# Schematic_altium.net
KiCad netlist of a schematic drawn in Altium Designer
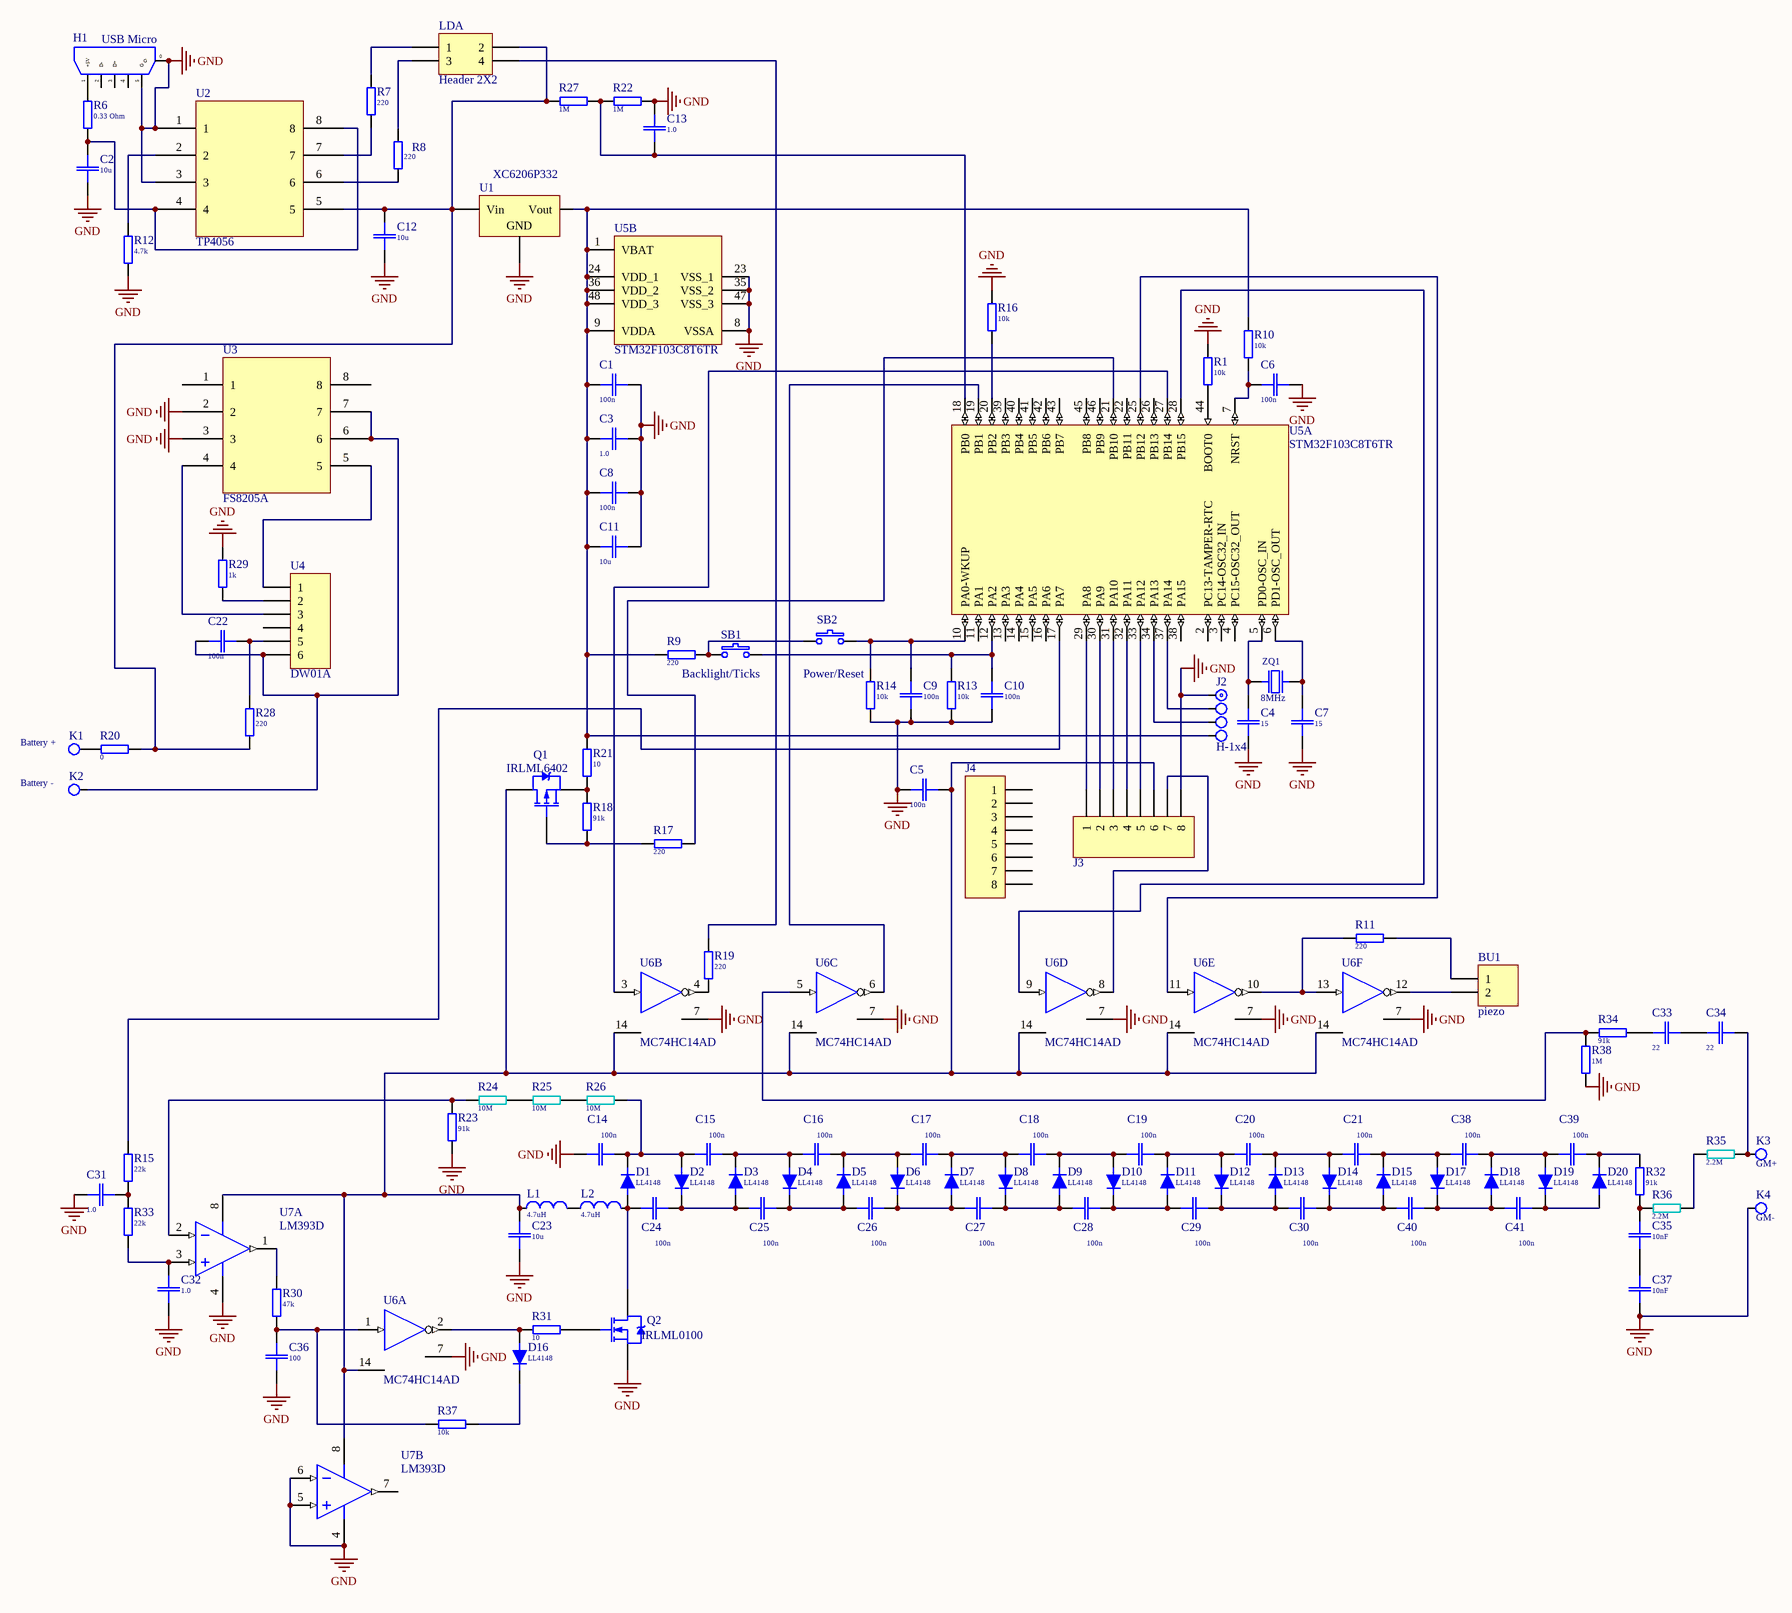
[diagram p0: Schematic_altium.SchDoc]

(export (version "E")
  (design (tool "Eeschema 10.0.6"))
  (components
    (comp (ref "BU1")
      (value "piezo")
      (footprint "HDR1X2")
      (description "Header, 2-Pin")
      (fields (field (name "PUBLISHER") "Altium Limited"))
      (libsource (lib "Miscellaneous Connectors") (part "Header 2"))
    )
    (comp (ref "C1")
      (value "100n")
      (footprint "C0805(2013)")
      (description "SMD-0805")
      (libsource (lib "SMD-RCL") (part "C-0805"))
    )
    (comp (ref "C2")
      (value "10u")
      (footprint "C1210(3225)")
      (description "SMD-1210 100V X7R 10%")
      (libsource (lib "SMD-RCL") (part "C-1210  100V 2.2u"))
    )
    (comp (ref "C3")
      (value "1.0")
      (footprint "C0805(2013)")
      (description "SMD-0805")
      (libsource (lib "SMD-RCL") (part "C-0805"))
    )
    (comp (ref "C4")
      (value "15")
      (footprint "C0805(2013)")
      (description "SMD-0805")
      (libsource (lib "SMD-RCL") (part "C-0805"))
    )
    (comp (ref "C5")
      (value "100n")
      (footprint "C0805(2013)")
      (description "SMD-0805")
      (libsource (lib "SMD-RCL") (part "C-0805"))
    )
    (comp (ref "C6")
      (value "100n")
      (footprint "C0805(2013)")
      (description "SMD-0805")
      (libsource (lib "SMD-RCL") (part "C-0805"))
    )
    (comp (ref "C7")
      (value "15")
      (footprint "C0805(2013)")
      (description "SMD-0805")
      (libsource (lib "SMD-RCL") (part "C-0805"))
    )
    (comp (ref "C8")
      (value "100n")
      (footprint "C0805(2013)")
      (description "SMD-0805")
      (libsource (lib "SMD-RCL") (part "C-0805"))
    )
    (comp (ref "C9")
      (value "100n")
      (footprint "C0805(2013)")
      (description "SMD-0805")
      (libsource (lib "SMD-RCL") (part "C-0805"))
    )
    (comp (ref "C10")
      (value "100n")
      (footprint "C0805(2013)")
      (description "SMD-0805")
      (libsource (lib "SMD-RCL") (part "C-0805"))
    )
    (comp (ref "C11")
      (value "10u")
      (footprint "C1210(3225)")
      (description "SMD-1210 100V X7R 10%")
      (libsource (lib "SMD-RCL") (part "C-1210  100V 2.2u"))
    )
    (comp (ref "C12")
      (value "10u")
      (footprint "C1210(3225)")
      (description "SMD-1210 100V X7R 10%")
      (libsource (lib "SMD-RCL") (part "C-1210  100V 2.2u"))
    )
    (comp (ref "C13")
      (value "1.0")
      (footprint "C0805(2013)")
      (description "SMD-0805")
      (libsource (lib "SMD-RCL") (part "C-0805"))
    )
    (comp (ref "C14")
      (value "100n")
      (footprint "C0805(2013)")
      (description "SMD-0805")
      (libsource (lib "SMD-RCL") (part "C-0805"))
    )
    (comp (ref "C15")
      (value "100n")
      (footprint "C0805(2013)")
      (description "SMD-0805")
      (libsource (lib "SMD-RCL") (part "C-0805"))
    )
    (comp (ref "C16")
      (value "100n")
      (footprint "C0805(2013)")
      (description "SMD-0805")
      (libsource (lib "SMD-RCL") (part "C-0805"))
    )
    (comp (ref "C17")
      (value "100n")
      (footprint "C0805(2013)")
      (description "SMD-0805")
      (libsource (lib "SMD-RCL") (part "C-0805"))
    )
    (comp (ref "C18")
      (value "100n")
      (footprint "C0805(2013)")
      (description "SMD-0805")
      (libsource (lib "SMD-RCL") (part "C-0805"))
    )
    (comp (ref "C19")
      (value "100n")
      (footprint "C0805(2013)")
      (description "SMD-0805")
      (libsource (lib "SMD-RCL") (part "C-0805"))
    )
    (comp (ref "C20")
      (value "100n")
      (footprint "C0805(2013)")
      (description "SMD-0805")
      (libsource (lib "SMD-RCL") (part "C-0805"))
    )
    (comp (ref "C21")
      (value "100n")
      (footprint "C0805(2013)")
      (description "SMD-0805")
      (libsource (lib "SMD-RCL") (part "C-0805"))
    )
    (comp (ref "C22")
      (value "100n")
      (footprint "C0805(2013)")
      (description "SMD-0805")
      (libsource (lib "SMD-RCL") (part "C-0805"))
    )
    (comp (ref "C23")
      (value "10u")
      (footprint "C1210(3225)")
      (description "SMD-1210 100V X7R 10%")
      (libsource (lib "SMD-RCL") (part "C-1210  100V 2.2u"))
    )
    (comp (ref "C24")
      (value "100n")
      (footprint "C0805(2013)")
      (description "SMD-0805")
      (libsource (lib "SMD-RCL") (part "C-0805"))
    )
    (comp (ref "C25")
      (value "100n")
      (footprint "C0805(2013)")
      (description "SMD-0805")
      (libsource (lib "SMD-RCL") (part "C-0805"))
    )
    (comp (ref "C26")
      (value "100n")
      (footprint "C0805(2013)")
      (description "SMD-0805")
      (libsource (lib "SMD-RCL") (part "C-0805"))
    )
    (comp (ref "C27")
      (value "100n")
      (footprint "C0805(2013)")
      (description "SMD-0805")
      (libsource (lib "SMD-RCL") (part "C-0805"))
    )
    (comp (ref "C28")
      (value "100n")
      (footprint "C0805(2013)")
      (description "SMD-0805")
      (libsource (lib "SMD-RCL") (part "C-0805"))
    )
    (comp (ref "C29")
      (value "100n")
      (footprint "C0805(2013)")
      (description "SMD-0805")
      (libsource (lib "SMD-RCL") (part "C-0805"))
    )
    (comp (ref "C30")
      (value "100n")
      (footprint "C0805(2013)")
      (description "SMD-0805")
      (libsource (lib "SMD-RCL") (part "C-0805"))
    )
    (comp (ref "C31")
      (value "1.0")
      (footprint "C0805(2013)")
      (description "SMD-0805")
      (libsource (lib "SMD-RCL") (part "C-0805"))
    )
    (comp (ref "C32")
      (value "1.0")
      (footprint "C0805(2013)")
      (description "SMD-0805")
      (libsource (lib "SMD-RCL") (part "C-0805"))
    )
    (comp (ref "C33")
      (value "22")
      (footprint "C1210(3225)")
      (description "SMD-1210 100V X7R 10%")
      (libsource (lib "SMD-RCL") (part "C-1210  100V 2.2u"))
    )
    (comp (ref "C34")
      (value "22")
      (footprint "C1210(3225)")
      (description "SMD-1210 100V X7R 10%")
      (libsource (lib "SMD-RCL") (part "C-1210  100V 2.2u"))
    )
    (comp (ref "C35")
      (value "10nF")
      (footprint "C1210(3225)")
      (description "SMD-1210 100V X7R 10%")
      (libsource (lib "SMD-RCL") (part "C-1210  100V 2.2u"))
    )
    (comp (ref "C36")
      (value "100")
      (footprint "C0805(2013)")
      (description "SMD-0805")
      (libsource (lib "SMD-RCL") (part "C-0805"))
    )
    (comp (ref "C37")
      (value "10nF")
      (footprint "C1210(3225)")
      (description "SMD-1210 100V X7R 10%")
      (libsource (lib "SMD-RCL") (part "C-1210  100V 2.2u"))
    )
    (comp (ref "C38")
      (value "100n")
      (footprint "C0805(2013)")
      (description "SMD-0805")
      (libsource (lib "SMD-RCL") (part "C-0805"))
    )
    (comp (ref "C39")
      (value "100n")
      (footprint "C0805(2013)")
      (description "SMD-0805")
      (libsource (lib "SMD-RCL") (part "C-0805"))
    )
    (comp (ref "C40")
      (value "100n")
      (footprint "C0805(2013)")
      (description "SMD-0805")
      (libsource (lib "SMD-RCL") (part "C-0805"))
    )
    (comp (ref "C41")
      (value "100n")
      (footprint "C0805(2013)")
      (description "SMD-0805")
      (libsource (lib "SMD-RCL") (part "C-0805"))
    )
    (comp (ref "D1")
      (value "LL4148")
      (footprint "SOD80/MLL34")
      (description "75V 0.3A SOD80/MLL34")
      (libsource (lib "Diodes") (part "LL4148"))
    )
    (comp (ref "D2")
      (value "LL4148")
      (footprint "SOD80/MLL34")
      (description "75V 0.3A SOD80/MLL34")
      (libsource (lib "Diodes") (part "LL4148"))
    )
    (comp (ref "D3")
      (value "LL4148")
      (footprint "SOD80/MLL34")
      (description "75V 0.3A SOD80/MLL34")
      (libsource (lib "Diodes") (part "LL4148"))
    )
    (comp (ref "D4")
      (value "LL4148")
      (footprint "SOD80/MLL34")
      (description "75V 0.3A SOD80/MLL34")
      (libsource (lib "Diodes") (part "LL4148"))
    )
    (comp (ref "D5")
      (value "LL4148")
      (footprint "SOD80/MLL34")
      (description "75V 0.3A SOD80/MLL34")
      (libsource (lib "Diodes") (part "LL4148"))
    )
    (comp (ref "D6")
      (value "LL4148")
      (footprint "SOD80/MLL34")
      (description "75V 0.3A SOD80/MLL34")
      (libsource (lib "Diodes") (part "LL4148"))
    )
    (comp (ref "D7")
      (value "LL4148")
      (footprint "SOD80/MLL34")
      (description "75V 0.3A SOD80/MLL34")
      (libsource (lib "Diodes") (part "LL4148"))
    )
    (comp (ref "D8")
      (value "LL4148")
      (footprint "SOD80/MLL34")
      (description "75V 0.3A SOD80/MLL34")
      (libsource (lib "Diodes") (part "LL4148"))
    )
    (comp (ref "D9")
      (value "LL4148")
      (footprint "SOD80/MLL34")
      (description "75V 0.3A SOD80/MLL34")
      (libsource (lib "Diodes") (part "LL4148"))
    )
    (comp (ref "D10")
      (value "LL4148")
      (footprint "SOD80/MLL34")
      (description "75V 0.3A SOD80/MLL34")
      (libsource (lib "Diodes") (part "LL4148"))
    )
    (comp (ref "D11")
      (value "LL4148")
      (footprint "SOD80/MLL34")
      (description "75V 0.3A SOD80/MLL34")
      (libsource (lib "Diodes") (part "LL4148"))
    )
    (comp (ref "D12")
      (value "LL4148")
      (footprint "SOD80/MLL34")
      (description "75V 0.3A SOD80/MLL34")
      (libsource (lib "Diodes") (part "LL4148"))
    )
    (comp (ref "D13")
      (value "LL4148")
      (footprint "SOD80/MLL34")
      (description "75V 0.3A SOD80/MLL34")
      (libsource (lib "Diodes") (part "LL4148"))
    )
    (comp (ref "D14")
      (value "LL4148")
      (footprint "SOD80/MLL34")
      (description "75V 0.3A SOD80/MLL34")
      (libsource (lib "Diodes") (part "LL4148"))
    )
    (comp (ref "D15")
      (value "LL4148")
      (footprint "SOD80/MLL34")
      (description "75V 0.3A SOD80/MLL34")
      (libsource (lib "Diodes") (part "LL4148"))
    )
    (comp (ref "D16")
      (value "LL4148")
      (footprint "SOD80/MLL34")
      (description "75V 0.3A SOD80/MLL34")
      (libsource (lib "Diodes") (part "LL4148"))
    )
    (comp (ref "D17")
      (value "LL4148")
      (footprint "SOD80/MLL34")
      (description "75V 0.3A SOD80/MLL34")
      (libsource (lib "Diodes") (part "LL4148"))
    )
    (comp (ref "D18")
      (value "LL4148")
      (footprint "SOD80/MLL34")
      (description "75V 0.3A SOD80/MLL34")
      (libsource (lib "Diodes") (part "LL4148"))
    )
    (comp (ref "D19")
      (value "LL4148")
      (footprint "SOD80/MLL34")
      (description "75V 0.3A SOD80/MLL34")
      (libsource (lib "Diodes") (part "LL4148"))
    )
    (comp (ref "D20")
      (value "LL4148")
      (footprint "SOD80/MLL34")
      (description "75V 0.3A SOD80/MLL34")
      (libsource (lib "Diodes") (part "LL4148"))
    )
    (comp (ref "H1")
      (value "USB Micro")
      (footprint "USB Micro")
      (description "USB B Micro R/A SMD")
      (libsource (lib "Connektor") (part "USB Micro"))
    )
    (comp (ref "J2") (value "H-1x4") (footprint "J1x4") (libsource (lib "Connektor") (part "H-1x4")))
    (comp (ref "J3")
      (value "~")
      (footprint "HDR1X8")
      (description "Header, 8-Pin")
      (fields (field (name "PUBLISHER") "Altium Limited"))
      (libsource (lib "Miscellaneous Connectors") (part "Header 8"))
    )
    (comp (ref "J4")
      (value "~")
      (footprint "HDR1X8")
      (description "Header, 8-Pin")
      (fields (field (name "PUBLISHER") "Altium Limited"))
      (libsource (lib "") (part "Header 8_1"))
    )
    (comp (ref "K1") (value "Battery +") (footprint "F1-2.5") (libsource (lib "Connektor") (part "K-1-2.5")))
    (comp (ref "K2") (value "Battery -") (footprint "F1-2.5") (libsource (lib "Connektor") (part "K-1-2.5")))
    (comp (ref "K3") (value "GM+") (footprint "F1-2.5") (libsource (lib "Connektor") (part "K-1-2.5")))
    (comp (ref "K4") (value "GM-") (footprint "F1-2.5") (libsource (lib "Connektor") (part "K-1-2.5")))
    (comp (ref "L1")
      (value "4.7uH")
      (footprint "Dr-SD-75")
      (description "1.2A 0.15om 7.3x7.3x5mm")
      (libsource (lib "SMD-RCL") (part "L-SD-75 33uH"))
    )
    (comp (ref "L2")
      (value "4.7uH")
      (footprint "Dr-SD-75")
      (description "1.2A 0.15om 7.3x7.3x5mm")
      (libsource (lib "SMD-RCL") (part "L-SD-75 33uH"))
    )
    (comp (ref "LDA")
      (value "Header 2X2")
      (footprint "HDR2X2")
      (description "Header, 2-Pin, Dual row")
      (fields (field (name "PUBLISHER") "Altium Limited"))
      (libsource (lib "Miscellaneous Connectors") (part "Header 2X2"))
    )
    (comp (ref "Q1")
      (value "IRLML6402")
      (footprint "Micro3_N")
      (description "HEXFET Power MOSFET")
      (fields (field (name "PUBLISHER") "Altium Limited"))
      (libsource (lib "IR Discrete MOSFET - Power") (part "IRLML6401"))
    )
    (comp (ref "Q2")
      (value "IRLML0100")
      (footprint "SOT-23_N")
      (description "HEXFET Power MOSFET")
      (fields (field (name "PUBLISHER") "Altium Limited"))
      (libsource (lib "IR Discrete MOSFET - Power") (part "IRLML2402"))
    )
    (comp (ref "R1")
      (value "10k")
      (footprint "R0805")
      (description "SMD 0805 0.1W 5% 150V")
      (libsource (lib "SMD-RCL") (part "R-0805"))
    )
    (comp (ref "R6")
      (value "0.33 Ohm")
      (footprint "R0805")
      (description "SMD 0805 0.1W 5% 150V")
      (libsource (lib "SMD-RCL") (part "R-0805"))
    )
    (comp (ref "R7")
      (value "220")
      (footprint "R0805")
      (description "SMD 0805 0.1W 5% 150V")
      (libsource (lib "SMD-RCL") (part "R-0805"))
    )
    (comp (ref "R8")
      (value "220")
      (footprint "R0805")
      (description "SMD 0805 0.1W 5% 150V")
      (libsource (lib "SMD-RCL") (part "R-0805"))
    )
    (comp (ref "R9")
      (value "220")
      (footprint "R0805")
      (description "SMD 0805 0.1W 5% 150V")
      (libsource (lib "SMD-RCL") (part "R-0805"))
    )
    (comp (ref "R10")
      (value "10k")
      (footprint "R0805")
      (description "SMD 0805 0.1W 5% 150V")
      (libsource (lib "SMD-RCL") (part "R-0805"))
    )
    (comp (ref "R11")
      (value "220")
      (footprint "R0805")
      (description "SMD 0805 0.1W 5% 150V")
      (libsource (lib "SMD-RCL") (part "R-0805"))
    )
    (comp (ref "R12")
      (value "4.7k")
      (footprint "R0805")
      (description "SMD 0805 0.1W 5% 150V")
      (libsource (lib "SMD-RCL") (part "R-0805"))
    )
    (comp (ref "R13")
      (value "10k")
      (footprint "R0805")
      (description "SMD 0805 0.1W 5% 150V")
      (libsource (lib "SMD-RCL") (part "R-0805"))
    )
    (comp (ref "R14")
      (value "10k")
      (footprint "R0805")
      (description "SMD 0805 0.1W 5% 150V")
      (libsource (lib "SMD-RCL") (part "R-0805"))
    )
    (comp (ref "R15")
      (value "22k")
      (footprint "R0805")
      (description "SMD 0805 0.1W 5% 150V")
      (libsource (lib "SMD-RCL") (part "R-0805"))
    )
    (comp (ref "R16")
      (value "10k")
      (footprint "R0805")
      (description "SMD 0805 0.1W 5% 150V")
      (libsource (lib "SMD-RCL") (part "R-0805"))
    )
    (comp (ref "R17")
      (value "220")
      (footprint "R0805")
      (description "SMD 0805 0.1W 5% 150V")
      (libsource (lib "SMD-RCL") (part "R-0805"))
    )
    (comp (ref "R18")
      (value "91k")
      (footprint "R0805")
      (description "SMD 0805 0.1W 5% 150V")
      (libsource (lib "SMD-RCL") (part "R-0805"))
    )
    (comp (ref "R19")
      (value "220")
      (footprint "R0805")
      (description "SMD 0805 0.1W 5% 150V")
      (libsource (lib "SMD-RCL") (part "R-0805"))
    )
    (comp (ref "R20")
      (value "0")
      (footprint "R0805")
      (description "SMD 0805 0.1W 5% 150V")
      (libsource (lib "SMD-RCL") (part "R-0805"))
    )
    (comp (ref "R21")
      (value "10")
      (footprint "R0805")
      (description "SMD 0805 0.1W 5% 150V")
      (libsource (lib "SMD-RCL") (part "R-0805"))
    )
    (comp (ref "R22")
      (value "1M")
      (footprint "R0805")
      (description "SMD 0805 0.1W 5% 150V")
      (libsource (lib "SMD-RCL") (part "R-0805"))
    )
    (comp (ref "R23")
      (value "91k")
      (footprint "R0805")
      (description "SMD 0805 0.1W 5% 150V")
      (libsource (lib "SMD-RCL") (part "R-0805"))
    )
    (comp (ref "R24")
      (value "10M")
      (footprint "R1206")
      (description "SMD 1206 0.125W 5% 200V")
      (libsource (lib "SMD-RCL") (part "R-1206"))
    )
    (comp (ref "R25")
      (value "10M")
      (footprint "R1206")
      (description "SMD 1206 0.125W 5% 200V")
      (libsource (lib "SMD-RCL") (part "R-1206"))
    )
    (comp (ref "R26")
      (value "10M")
      (footprint "R1206")
      (description "SMD 1206 0.125W 5% 200V")
      (libsource (lib "SMD-RCL") (part "R-1206"))
    )
    (comp (ref "R27")
      (value "1M")
      (footprint "R0805")
      (description "SMD 0805 0.1W 5% 150V")
      (libsource (lib "SMD-RCL") (part "R-0805"))
    )
    (comp (ref "R28")
      (value "220")
      (footprint "R0805")
      (description "SMD 0805 0.1W 5% 150V")
      (libsource (lib "SMD-RCL") (part "R-0805"))
    )
    (comp (ref "R29")
      (value "1k")
      (footprint "R0805")
      (description "SMD 0805 0.1W 5% 150V")
      (libsource (lib "SMD-RCL") (part "R-0805"))
    )
    (comp (ref "R30")
      (value "47k")
      (footprint "R0805")
      (description "SMD 0805 0.1W 5% 150V")
      (libsource (lib "SMD-RCL") (part "R-0805"))
    )
    (comp (ref "R31")
      (value "10")
      (footprint "R0805")
      (description "SMD 0805 0.1W 5% 150V")
      (libsource (lib "SMD-RCL") (part "R-0805"))
    )
    (comp (ref "R32")
      (value "91k")
      (footprint "R0805")
      (description "SMD 0805 0.1W 5% 150V")
      (libsource (lib "SMD-RCL") (part "R-0805"))
    )
    (comp (ref "R33")
      (value "22k")
      (footprint "R0805")
      (description "SMD 0805 0.1W 5% 150V")
      (libsource (lib "SMD-RCL") (part "R-0805"))
    )
    (comp (ref "R34")
      (value "91k")
      (footprint "R0805")
      (description "SMD 0805 0.1W 5% 150V")
      (libsource (lib "SMD-RCL") (part "R-0805"))
    )
    (comp (ref "R35")
      (value "2.2M")
      (footprint "R1206")
      (description "SMD 1206 0.125W 5% 200V")
      (libsource (lib "SMD-RCL") (part "R-1206"))
    )
    (comp (ref "R36")
      (value "2.2M")
      (footprint "R1206")
      (description "SMD 1206 0.125W 5% 200V")
      (libsource (lib "SMD-RCL") (part "R-1206"))
    )
    (comp (ref "R37")
      (value "10k")
      (footprint "R0805")
      (description "SMD 0805 0.1W 5% 150V")
      (libsource (lib "SMD-RCL") (part "R-0805"))
    )
    (comp (ref "R38")
      (value "1M")
      (footprint "R0805")
      (description "SMD 0805 0.1W 5% 150V")
      (libsource (lib "SMD-RCL") (part "R-0805"))
    )
    (comp (ref "SB1")
      (value "Backlight/Ticks")
      (footprint "TS-06")
      (libsource (lib "Devise") (part "Buton TS-06"))
    )
    (comp (ref "SB2")
      (value "Power/Reset")
      (footprint "TS-06")
      (libsource (lib "Devise") (part "Buton TS-06"))
    )
    (comp (ref "U1")
      (value "XC6206P332")
      (footprint "SOT23_N")
      (description "Voltage Regulator")
      (fields (field (name "PUBLISHER") "Altium Limited"))
      (libsource (lib "Miscellaneous Devices") (part "Volt Reg"))
    )
    (comp (ref "U2") (value "TP4056") (footprint "751-06_N") (libsource (lib "Schlib1") (part "MP2307")))
    (comp (ref "U3") (value "FS8205A") (footprint "SOP65P780-8M") (libsource (lib "Schlib1") (part "MP2307")))
    (comp (ref "U4")
      (value "DW01A")
      (footprint "SOT363-6N")
      (description "Header, 6-Pin")
      (fields (field (name "PUBLISHER") "Altium Limited"))
      (libsource (lib "Miscellaneous Connectors") (part "Header 6"))
    )
    (comp (ref "U5")
      (value "STM32F103C8T6TR")
      (footprint "STM-LQFP48_N")
      (libsource (lib "STMicroelectronics STM32 F1") (part "STM32F103C8T6TR"))
    )
    (comp (ref "U6")
      (value "MC74HC14AD")
      (footprint "751A-02_N")
      (description "Hex Schmitt Trigger Inverter")
      (fields (field (name "PUBLISHER") "Altium Limited"))
      (libsource (lib "Motorola Logic Gate") (part "MC74HC14AD"))
    )
    (comp (ref "U7")
      (value "LM393D")
      (footprint "751-02_N")
      (description "Dual Comparator")
      (fields (field (name "PUBLISHER") "Altium Limited"))
      (libsource (lib "Motorola Analog Comparator") (part "LM393D"))
    )
    (comp (ref "ZQ1") (value "8MHz") (footprint "HC49S") (libsource (lib "Devise") (part "Q")))
  )
  (nets
    (net (code "1") (name "GND") (class "Default")
      (node (ref "C1") (pin "2") (pinfunction "2_2") (pintype "passive"))
      (node (ref "C10") (pin "1") (pinfunction "1_1") (pintype "passive"))
      (node (ref "C11") (pin "2") (pinfunction "2_2") (pintype "passive"))
      (node (ref "C12") (pin "2") (pinfunction "2_2") (pintype "passive"))
      (node (ref "C13") (pin "2") (pinfunction "2_2") (pintype "passive"))
      (node (ref "C14") (pin "1") (pinfunction "1_1") (pintype "passive"))
      (node (ref "C2") (pin "2") (pinfunction "2_2") (pintype "passive"))
      (node (ref "C23") (pin "2") (pinfunction "2_2") (pintype "passive"))
      (node (ref "C3") (pin "2") (pinfunction "2_2") (pintype "passive"))
      (node (ref "C31") (pin "1") (pinfunction "1_1") (pintype "passive"))
      (node (ref "C32") (pin "1") (pinfunction "1_1") (pintype "passive"))
      (node (ref "C36") (pin "1") (pinfunction "1_1") (pintype "passive"))
      (node (ref "C37") (pin "2") (pinfunction "2_2") (pintype "passive"))
      (node (ref "C4") (pin "2") (pinfunction "2_2") (pintype "passive"))
      (node (ref "C5") (pin "1") (pinfunction "1_1") (pintype "passive"))
      (node (ref "C6") (pin "2") (pinfunction "2_2") (pintype "passive"))
      (node (ref "C7") (pin "2") (pinfunction "2_2") (pintype "passive"))
      (node (ref "C8") (pin "2") (pinfunction "2_2") (pintype "passive"))
      (node (ref "C9") (pin "1") (pinfunction "1_1") (pintype "passive"))
      (node (ref "H1") (pin "0") (pinfunction "G_0") (pintype "passive"))
      (node (ref "H1") (pin "5") (pinfunction "G_5") (pintype "passive"))
      (node (ref "J2") (pin "1") (pinfunction "1_1") (pintype "passive"))
      (node (ref "J3") (pin "8") (pinfunction "8_8") (pintype "passive"))
      (node (ref "K4") (pin "1") (pinfunction "1_1") (pintype "passive"))
      (node (ref "Q2") (pin "2") (pinfunction "S_2") (pintype "passive"))
      (node (ref "R1") (pin "2") (pinfunction "2_2") (pintype "passive"))
      (node (ref "R12") (pin "1") (pinfunction "1_1") (pintype "passive"))
      (node (ref "R13") (pin "1") (pinfunction "1_1") (pintype "passive"))
      (node (ref "R14") (pin "1") (pinfunction "1_1") (pintype "passive"))
      (node (ref "R16") (pin "2") (pinfunction "2_2") (pintype "passive"))
      (node (ref "R22") (pin "1") (pinfunction "1_1") (pintype "passive"))
      (node (ref "R23") (pin "2") (pinfunction "2_2") (pintype "passive"))
      (node (ref "R29") (pin "2") (pinfunction "2_2") (pintype "passive"))
      (node (ref "R38") (pin "1") (pinfunction "1_1") (pintype "passive"))
      (node (ref "U1") (pin "2") (pinfunction "GND_2") (pintype "passive"))
      (node (ref "U2") (pin "1") (pinfunction "1_1") (pintype "passive"))
      (node (ref "U2") (pin "3") (pinfunction "3_3") (pintype "passive"))
      (node (ref "U3") (pin "2") (pinfunction "2_2") (pintype "passive"))
      (node (ref "U3") (pin "3") (pinfunction "3_3") (pintype "passive"))
      (node (ref "U5") (pin "23") (pinfunction "VSS_1_23") (pintype "power_in"))
      (node (ref "U5") (pin "35") (pinfunction "VSS_2_35") (pintype "power_in"))
      (node (ref "U5") (pin "47") (pinfunction "VSS_3_47") (pintype "power_in"))
      (node (ref "U5") (pin "8") (pinfunction "VSSA_8") (pintype "power_in"))
      (node (ref "U6") (pin "7") (pinfunction "GND_7") (pintype "power_in"))
      (node (ref "U7") (pin "4") (pinfunction "GND_4") (pintype "power_in"))
      (node (ref "U7") (pin "5") (pinfunction "IN+_5") (pintype "input"))
      (node (ref "U7") (pin "6") (pinfunction "IN-_6") (pintype "input"))
    )
    (net (code "2") (name "Net-(BU1-Pad1)") (class "Default")
      (node (ref "BU1") (pin "1") (pinfunction "1_1") (pintype "passive"))
      (node (ref "R11") (pin "1") (pinfunction "1_1") (pintype "passive"))
    )
    (net (code "3") (name "Net-(C2-Pad1)") (class "Default")
      (node (ref "C2") (pin "1") (pinfunction "1_1") (pintype "passive"))
      (node (ref "R6") (pin "1") (pinfunction "1_1") (pintype "passive"))
      (node (ref "U2") (pin "4") (pinfunction "4_4") (pintype "passive"))
      (node (ref "U2") (pin "8") (pinfunction "8_8") (pintype "passive"))
    )
    (net (code "4") (name "Net-(C22-Pad1)") (class "Default")
      (node (ref "C22") (pin "1") (pinfunction "1_1") (pintype "passive"))
      (node (ref "K2") (pin "1") (pinfunction "1_1") (pintype "passive"))
      (node (ref "U3") (pin "6") (pinfunction "6_6") (pintype "passive"))
      (node (ref "U3") (pin "7") (pinfunction "7_7") (pintype "passive"))
      (node (ref "U4") (pin "6") (pinfunction "6_6") (pintype "passive"))
    )
    (net (code "5") (name "Net-(C22-Pad2)") (class "Default")
      (node (ref "C22") (pin "2") (pinfunction "2_2") (pintype "passive"))
      (node (ref "R28") (pin "2") (pinfunction "2_2") (pintype "passive"))
      (node (ref "U4") (pin "5") (pinfunction "5_5") (pintype "passive"))
    )
    (net (code "6") (name "Net-(C31-Pad2)") (class "Default")
      (node (ref "C31") (pin "2") (pinfunction "2_2") (pintype "passive"))
      (node (ref "R15") (pin "1") (pinfunction "1_1") (pintype "passive"))
      (node (ref "R33") (pin "2") (pinfunction "2_2") (pintype "passive"))
    )
    (net (code "7") (name "Net-(C33-Pad1)") (class "Default")
      (node (ref "C33") (pin "1") (pinfunction "1_1") (pintype "passive"))
      (node (ref "R34") (pin "1") (pinfunction "1_1") (pintype "passive"))
    )
    (net (code "8") (name "Net-(C33-Pad2)") (class "Default")
      (node (ref "C33") (pin "2") (pinfunction "2_2") (pintype "passive"))
      (node (ref "C34") (pin "1") (pinfunction "1_1") (pintype "passive"))
    )
    (net (code "9") (name "Net-(C34-Pad2)") (class "Default")
      (node (ref "C34") (pin "2") (pinfunction "2_2") (pintype "passive"))
      (node (ref "K3") (pin "1") (pinfunction "1_1") (pintype "passive"))
      (node (ref "R35") (pin "1") (pinfunction "1_1") (pintype "passive"))
    )
    (net (code "10") (name "Net-(C35-Pad1)") (class "Default")
      (node (ref "C35") (pin "1") (pinfunction "1_1") (pintype "passive"))
      (node (ref "R32") (pin "1") (pinfunction "1_1") (pintype "passive"))
      (node (ref "R36") (pin "2") (pinfunction "2_2") (pintype "passive"))
    )
    (net (code "11") (name "Net-(C35-Pad2)") (class "Default")
      (node (ref "C35") (pin "2") (pinfunction "2_2") (pintype "passive"))
      (node (ref "C37") (pin "1") (pinfunction "1_1") (pintype "passive"))
    )
    (net (code "12") (name "Net-(D1-A)") (class "Default")
      (node (ref "C24") (pin "1") (pinfunction "1_1") (pintype "passive"))
      (node (ref "D1") (pin "1") (pinfunction "A_1") (pintype "passive"))
      (node (ref "L2") (pin "2") (pinfunction "2_2") (pintype "passive"))
      (node (ref "Q2") (pin "3") (pinfunction "D_3") (pintype "passive"))
    )
    (net (code "13") (name "Net-(D1-C)") (class "Default")
      (node (ref "C14") (pin "2") (pinfunction "2_2") (pintype "passive"))
      (node (ref "C15") (pin "1") (pinfunction "1_1") (pintype "passive"))
      (node (ref "D1") (pin "2") (pinfunction "C_2") (pintype "passive"))
      (node (ref "D2") (pin "1") (pinfunction "A_1") (pintype "passive"))
      (node (ref "R26") (pin "1") (pinfunction "1_1") (pintype "passive"))
    )
    (net (code "14") (name "Net-(D2-C)") (class "Default")
      (node (ref "C24") (pin "2") (pinfunction "2_2") (pintype "passive"))
      (node (ref "C25") (pin "1") (pinfunction "1_1") (pintype "passive"))
      (node (ref "D2") (pin "2") (pinfunction "C_2") (pintype "passive"))
      (node (ref "D3") (pin "1") (pinfunction "A_1") (pintype "passive"))
    )
    (net (code "15") (name "Net-(D3-C)") (class "Default")
      (node (ref "C15") (pin "2") (pinfunction "2_2") (pintype "passive"))
      (node (ref "C16") (pin "1") (pinfunction "1_1") (pintype "passive"))
      (node (ref "D3") (pin "2") (pinfunction "C_2") (pintype "passive"))
      (node (ref "D4") (pin "1") (pinfunction "A_1") (pintype "passive"))
    )
    (net (code "16") (name "Net-(D4-C)") (class "Default")
      (node (ref "C25") (pin "2") (pinfunction "2_2") (pintype "passive"))
      (node (ref "C26") (pin "1") (pinfunction "1_1") (pintype "passive"))
      (node (ref "D4") (pin "2") (pinfunction "C_2") (pintype "passive"))
      (node (ref "D5") (pin "1") (pinfunction "A_1") (pintype "passive"))
    )
    (net (code "17") (name "Net-(D5-C)") (class "Default")
      (node (ref "C16") (pin "2") (pinfunction "2_2") (pintype "passive"))
      (node (ref "C17") (pin "1") (pinfunction "1_1") (pintype "passive"))
      (node (ref "D5") (pin "2") (pinfunction "C_2") (pintype "passive"))
      (node (ref "D6") (pin "1") (pinfunction "A_1") (pintype "passive"))
    )
    (net (code "18") (name "Net-(D6-C)") (class "Default")
      (node (ref "C26") (pin "2") (pinfunction "2_2") (pintype "passive"))
      (node (ref "C27") (pin "1") (pinfunction "1_1") (pintype "passive"))
      (node (ref "D6") (pin "2") (pinfunction "C_2") (pintype "passive"))
      (node (ref "D7") (pin "1") (pinfunction "A_1") (pintype "passive"))
    )
    (net (code "19") (name "Net-(D7-C)") (class "Default")
      (node (ref "C17") (pin "2") (pinfunction "2_2") (pintype "passive"))
      (node (ref "C18") (pin "1") (pinfunction "1_1") (pintype "passive"))
      (node (ref "D7") (pin "2") (pinfunction "C_2") (pintype "passive"))
      (node (ref "D8") (pin "1") (pinfunction "A_1") (pintype "passive"))
    )
    (net (code "20") (name "Net-(D8-C)") (class "Default")
      (node (ref "C27") (pin "2") (pinfunction "2_2") (pintype "passive"))
      (node (ref "C28") (pin "1") (pinfunction "1_1") (pintype "passive"))
      (node (ref "D8") (pin "2") (pinfunction "C_2") (pintype "passive"))
      (node (ref "D9") (pin "1") (pinfunction "A_1") (pintype "passive"))
    )
    (net (code "21") (name "Net-(D10-A)") (class "Default")
      (node (ref "C18") (pin "2") (pinfunction "2_2") (pintype "passive"))
      (node (ref "C19") (pin "1") (pinfunction "1_1") (pintype "passive"))
      (node (ref "D10") (pin "1") (pinfunction "A_1") (pintype "passive"))
      (node (ref "D9") (pin "2") (pinfunction "C_2") (pintype "passive"))
    )
    (net (code "22") (name "Net-(D10-C)") (class "Default")
      (node (ref "C28") (pin "2") (pinfunction "2_2") (pintype "passive"))
      (node (ref "C29") (pin "1") (pinfunction "1_1") (pintype "passive"))
      (node (ref "D10") (pin "2") (pinfunction "C_2") (pintype "passive"))
      (node (ref "D11") (pin "1") (pinfunction "A_1") (pintype "passive"))
    )
    (net (code "23") (name "Net-(D11-C)") (class "Default")
      (node (ref "C19") (pin "2") (pinfunction "2_2") (pintype "passive"))
      (node (ref "C20") (pin "1") (pinfunction "1_1") (pintype "passive"))
      (node (ref "D11") (pin "2") (pinfunction "C_2") (pintype "passive"))
      (node (ref "D12") (pin "1") (pinfunction "A_1") (pintype "passive"))
    )
    (net (code "24") (name "Net-(D12-C)") (class "Default")
      (node (ref "C29") (pin "2") (pinfunction "2_2") (pintype "passive"))
      (node (ref "C30") (pin "1") (pinfunction "1_1") (pintype "passive"))
      (node (ref "D12") (pin "2") (pinfunction "C_2") (pintype "passive"))
      (node (ref "D13") (pin "1") (pinfunction "A_1") (pintype "passive"))
    )
    (net (code "25") (name "Net-(D13-C)") (class "Default")
      (node (ref "C20") (pin "2") (pinfunction "2_2") (pintype "passive"))
      (node (ref "C21") (pin "1") (pinfunction "1_1") (pintype "passive"))
      (node (ref "D13") (pin "2") (pinfunction "C_2") (pintype "passive"))
      (node (ref "D14") (pin "1") (pinfunction "A_1") (pintype "passive"))
    )
    (net (code "26") (name "Net-(D14-C)") (class "Default")
      (node (ref "C30") (pin "2") (pinfunction "2_2") (pintype "passive"))
      (node (ref "C40") (pin "1") (pinfunction "1_1") (pintype "passive"))
      (node (ref "D14") (pin "2") (pinfunction "C_2") (pintype "passive"))
      (node (ref "D15") (pin "1") (pinfunction "A_1") (pintype "passive"))
    )
    (net (code "27") (name "Net-(D15-C)") (class "Default")
      (node (ref "C21") (pin "2") (pinfunction "2_2") (pintype "passive"))
      (node (ref "C38") (pin "1") (pinfunction "1_1") (pintype "passive"))
      (node (ref "D15") (pin "2") (pinfunction "C_2") (pintype "passive"))
      (node (ref "D17") (pin "1") (pinfunction "A_1") (pintype "passive"))
    )
    (net (code "28") (name "Net-(D16-A)") (class "Default")
      (node (ref "D16") (pin "1") (pinfunction "A_1") (pintype "passive"))
      (node (ref "R31") (pin "2") (pinfunction "2_2") (pintype "passive"))
      (node (ref "U6") (pin "2") (pinfunction "Y_2") (pintype "output"))
    )
    (net (code "29") (name "Net-(D16-C)") (class "Default")
      (node (ref "D16") (pin "2") (pinfunction "C_2") (pintype "passive"))
      (node (ref "R37") (pin "1") (pinfunction "1_1") (pintype "passive"))
    )
    (net (code "30") (name "Net-(D17-C)") (class "Default")
      (node (ref "C40") (pin "2") (pinfunction "2_2") (pintype "passive"))
      (node (ref "C41") (pin "1") (pinfunction "1_1") (pintype "passive"))
      (node (ref "D17") (pin "2") (pinfunction "C_2") (pintype "passive"))
      (node (ref "D18") (pin "1") (pinfunction "A_1") (pintype "passive"))
    )
    (net (code "31") (name "Net-(D18-C)") (class "Default")
      (node (ref "C38") (pin "2") (pinfunction "2_2") (pintype "passive"))
      (node (ref "C39") (pin "1") (pinfunction "1_1") (pintype "passive"))
      (node (ref "D18") (pin "2") (pinfunction "C_2") (pintype "passive"))
      (node (ref "D19") (pin "1") (pinfunction "A_1") (pintype "passive"))
    )
    (net (code "32") (name "Net-(D19-C)") (class "Default")
      (node (ref "C41") (pin "2") (pinfunction "2_2") (pintype "passive"))
      (node (ref "D19") (pin "2") (pinfunction "C_2") (pintype "passive"))
      (node (ref "D20") (pin "1") (pinfunction "A_1") (pintype "passive"))
    )
    (net (code "33") (name "Net-(D20-C)") (class "Default")
      (node (ref "C39") (pin "2") (pinfunction "2_2") (pintype "passive"))
      (node (ref "D20") (pin "2") (pinfunction "C_2") (pintype "passive"))
      (node (ref "R32") (pin "2") (pinfunction "2_2") (pintype "passive"))
    )
    (net (code "34") (name "Net-(H1-+5V)") (class "Default")
      (node (ref "H1") (pin "1") (pinfunction "+5V_1") (pintype "passive"))
      (node (ref "R6") (pin "2") (pinfunction "2_2") (pintype "passive"))
    )
    (net (code "35") (name "Net-(K1-Pad1)") (class "Default")
      (node (ref "K1") (pin "1") (pinfunction "1_1") (pintype "passive"))
      (node (ref "R20") (pin "2") (pinfunction "2_2") (pintype "passive"))
    )
    (net (code "36") (name "Net-(L1-Pad2)") (class "Default")
      (node (ref "L1") (pin "2") (pinfunction "2_2") (pintype "passive"))
      (node (ref "L2") (pin "1") (pinfunction "1_1") (pintype "passive"))
    )
    (net (code "37") (name "Net-(LDA-Pad1)") (class "Default")
      (node (ref "LDA") (pin "1") (pinfunction "1_1") (pintype "passive"))
      (node (ref "R7") (pin "2") (pinfunction "2_2") (pintype "passive"))
    )
    (net (code "38") (name "Net-(LDA-Pad3)") (class "Default")
      (node (ref "LDA") (pin "3") (pinfunction "3_3") (pintype "passive"))
      (node (ref "R8") (pin "2") (pinfunction "2_2") (pintype "passive"))
    )
    (net (code "39") (name "Net-(LDA-Pad4)") (class "Default")
      (node (ref "LDA") (pin "4") (pinfunction "4_4") (pintype "passive"))
      (node (ref "R19") (pin "2") (pinfunction "2_2") (pintype "passive"))
    )
    (net (code "40") (name "Net-(Q1-G)") (class "Default")
      (node (ref "Q1") (pin "1") (pinfunction "G_1") (pintype "passive"))
      (node (ref "R17") (pin "2") (pinfunction "2_2") (pintype "passive"))
      (node (ref "R18") (pin "1") (pinfunction "1_1") (pintype "passive"))
    )
    (net (code "41") (name "Net-(Q1-S)") (class "Default")
      (node (ref "Q1") (pin "2") (pinfunction "S_2") (pintype "passive"))
      (node (ref "R18") (pin "2") (pinfunction "2_2") (pintype "passive"))
      (node (ref "R21") (pin "1") (pinfunction "1_1") (pintype "passive"))
    )
    (net (code "42") (name "Net-(Q2-G)") (class "Default")
      (node (ref "Q2") (pin "1") (pinfunction "G_1") (pintype "passive"))
      (node (ref "R31") (pin "1") (pinfunction "1_1") (pintype "passive"))
    )
    (net (code "43") (name "Net-(R7-Pad1)") (class "Default")
      (node (ref "R7") (pin "1") (pinfunction "1_1") (pintype "passive"))
      (node (ref "U2") (pin "7") (pinfunction "7_7") (pintype "passive"))
    )
    (net (code "44") (name "Net-(R8-Pad1)") (class "Default")
      (node (ref "R8") (pin "1") (pinfunction "1_1") (pintype "passive"))
      (node (ref "U2") (pin "6") (pinfunction "6_6") (pintype "passive"))
    )
    (net (code "45") (name "Net-(R9-Pad1)") (class "Default")
      (node (ref "R9") (pin "1") (pinfunction "1_1") (pintype "passive"))
      (node (ref "SB1") (pin "1") (pinfunction "1_1") (pintype "passive"))
      (node (ref "SB2") (pin "1") (pinfunction "1_1") (pintype "passive"))
    )
    (net (code "46") (name "Net-(R12-Pad2)") (class "Default")
      (node (ref "R12") (pin "2") (pinfunction "2_2") (pintype "passive"))
      (node (ref "U2") (pin "2") (pinfunction "2_2") (pintype "passive"))
    )
    (net (code "47") (name "Net-(R24-Pad1)") (class "Default")
      (node (ref "R24") (pin "1") (pinfunction "1_1") (pintype "passive"))
      (node (ref "R25") (pin "2") (pinfunction "2_2") (pintype "passive"))
    )
    (net (code "48") (name "Net-(R25-Pad1)") (class "Default")
      (node (ref "R25") (pin "1") (pinfunction "1_1") (pintype "passive"))
      (node (ref "R26") (pin "2") (pinfunction "2_2") (pintype "passive"))
    )
    (net (code "49") (name "Net-(R29-Pad1)") (class "Default")
      (node (ref "R29") (pin "1") (pinfunction "1_1") (pintype "passive"))
      (node (ref "U4") (pin "2") (pinfunction "2_2") (pintype "passive"))
    )
    (net (code "50") (name "Net-(R35-Pad2)") (class "Default")
      (node (ref "R35") (pin "2") (pinfunction "2_2") (pintype "passive"))
      (node (ref "R36") (pin "1") (pinfunction "1_1") (pintype "passive"))
    )
    (net (code "51") (name "Net-(U1-Vin)") (class "Default")
      (node (ref "C12") (pin "1") (pinfunction "1_1") (pintype "passive"))
      (node (ref "LDA") (pin "2") (pinfunction "2_2") (pintype "passive"))
      (node (ref "R20") (pin "1") (pinfunction "1_1") (pintype "passive"))
      (node (ref "R27") (pin "2") (pinfunction "2_2") (pintype "passive"))
      (node (ref "R28") (pin "1") (pinfunction "1_1") (pintype "passive"))
      (node (ref "U1") (pin "1") (pinfunction "Vin_1") (pintype "passive"))
      (node (ref "U2") (pin "5") (pinfunction "5_5") (pintype "passive"))
    )
    (net (code "52") (name "Net-(U1-Vout)") (class "Default")
      (node (ref "C1") (pin "1") (pinfunction "1_1") (pintype "passive"))
      (node (ref "C11") (pin "1") (pinfunction "1_1") (pintype "passive"))
      (node (ref "C3") (pin "1") (pinfunction "1_1") (pintype "passive"))
      (node (ref "C8") (pin "1") (pinfunction "1_1") (pintype "passive"))
      (node (ref "J2") (pin "4") (pinfunction "4_4") (pintype "passive"))
      (node (ref "R10") (pin "2") (pinfunction "2_2") (pintype "passive"))
      (node (ref "R21") (pin "2") (pinfunction "2_2") (pintype "passive"))
      (node (ref "R9") (pin "2") (pinfunction "2_2") (pintype "passive"))
      (node (ref "U1") (pin "3") (pinfunction "Vout_3") (pintype "passive"))
      (node (ref "U5") (pin "1") (pinfunction "VBAT_1") (pintype "power_in"))
      (node (ref "U5") (pin "24") (pinfunction "VDD_1_24") (pintype "power_in"))
      (node (ref "U5") (pin "36") (pinfunction "VDD_2_36") (pintype "power_in"))
      (node (ref "U5") (pin "48") (pinfunction "VDD_3_48") (pintype "power_in"))
      (node (ref "U5") (pin "9") (pinfunction "VDDA_9") (pintype "power_in"))
    )
    (net (code "53") (name "Net-(U3-Pad4)") (class "Default")
      (node (ref "U3") (pin "4") (pinfunction "4_4") (pintype "passive"))
      (node (ref "U4") (pin "3") (pinfunction "3_3") (pintype "passive"))
    )
    (net (code "54") (name "Net-(U3-Pad5)") (class "Default")
      (node (ref "U3") (pin "5") (pinfunction "5_5") (pintype "passive"))
      (node (ref "U4") (pin "1") (pinfunction "1_1") (pintype "passive"))
    )
    (net (code "55") (name "Net-(U5A-BOOT0)") (class "Default")
      (node (ref "R1") (pin "1") (pinfunction "1_1") (pintype "passive"))
      (node (ref "U5") (pin "44") (pinfunction "BOOT0_44") (pintype "input"))
    )
    (net (code "56") (name "Net-(U5A-NRST)") (class "Default")
      (node (ref "C6") (pin "1") (pinfunction "1_1") (pintype "passive"))
      (node (ref "R10") (pin "1") (pinfunction "1_1") (pintype "passive"))
      (node (ref "U5") (pin "7") (pinfunction "NRST_7") (pintype "bidirectional"))
    )
    (net (code "57") (name "Net-(U5A-PA0-WKUP)") (class "Default")
      (node (ref "C9") (pin "2") (pinfunction "2_2") (pintype "passive"))
      (node (ref "R14") (pin "2") (pinfunction "2_2") (pintype "passive"))
      (node (ref "SB2") (pin "2") (pinfunction "2_2") (pintype "passive"))
      (node (ref "U5") (pin "10") (pinfunction "PA0-WKUP_10") (pintype "bidirectional"))
    )
    (net (code "58") (name "Net-(U5A-PA2)") (class "Default")
      (node (ref "C10") (pin "2") (pinfunction "2_2") (pintype "passive"))
      (node (ref "R13") (pin "2") (pinfunction "2_2") (pintype "passive"))
      (node (ref "SB1") (pin "2") (pinfunction "2_2") (pintype "passive"))
      (node (ref "U5") (pin "12") (pinfunction "PA2_12") (pintype "bidirectional"))
    )
    (net (code "59") (name "Net-(U5A-PA7)") (class "Default")
      (node (ref "R15") (pin "2") (pinfunction "2_2") (pintype "passive"))
      (node (ref "U5") (pin "17") (pinfunction "PA7_17") (pintype "bidirectional"))
    )
    (net (code "60") (name "Net-(U5A-PA8)") (class "Default")
      (node (ref "J3") (pin "1") (pinfunction "1_1") (pintype "passive"))
      (node (ref "U5") (pin "29") (pinfunction "PA8_29") (pintype "bidirectional"))
    )
    (net (code "61") (name "Net-(U5A-PA9)") (class "Default")
      (node (ref "J3") (pin "2") (pinfunction "2_2") (pintype "passive"))
      (node (ref "U5") (pin "30") (pinfunction "PA9_30") (pintype "bidirectional"))
    )
    (net (code "62") (name "Net-(U5A-PA10)") (class "Default")
      (node (ref "J3") (pin "3") (pinfunction "3_3") (pintype "passive"))
      (node (ref "U5") (pin "31") (pinfunction "PA10_31") (pintype "bidirectional"))
    )
    (net (code "63") (name "Net-(U5A-PA11)") (class "Default")
      (node (ref "J3") (pin "4") (pinfunction "4_4") (pintype "passive"))
      (node (ref "U5") (pin "32") (pinfunction "PA11_32") (pintype "bidirectional"))
    )
    (net (code "64") (name "Net-(U5A-PA12)") (class "Default")
      (node (ref "J3") (pin "5") (pinfunction "5_5") (pintype "passive"))
      (node (ref "U5") (pin "33") (pinfunction "PA12_33") (pintype "bidirectional"))
    )
    (net (code "65") (name "Net-(U5A-PA13)") (class "Default")
      (node (ref "J2") (pin "3") (pinfunction "3_3") (pintype "passive"))
      (node (ref "U5") (pin "34") (pinfunction "PA13_34") (pintype "bidirectional"))
    )
    (net (code "66") (name "Net-(U5A-PA14)") (class "Default")
      (node (ref "J2") (pin "2") (pinfunction "2_2") (pintype "passive"))
      (node (ref "U5") (pin "37") (pinfunction "PA14_37") (pintype "bidirectional"))
    )
    (net (code "67") (name "Net-(U5A-PB0)") (class "Default")
      (node (ref "C13") (pin "1") (pinfunction "1_1") (pintype "passive"))
      (node (ref "R22") (pin "2") (pinfunction "2_2") (pintype "passive"))
      (node (ref "R27") (pin "1") (pinfunction "1_1") (pintype "passive"))
      (node (ref "U5") (pin "18") (pinfunction "PB0_18") (pintype "bidirectional"))
    )
    (net (code "68") (name "Net-(U5A-PB1)") (class "Default")
      (node (ref "U5") (pin "19") (pinfunction "PB1_19") (pintype "bidirectional"))
      (node (ref "U6") (pin "6") (pinfunction "Y_6") (pintype "output"))
    )
    (net (code "69") (name "Net-(U5A-PB2)") (class "Default")
      (node (ref "R16") (pin "1") (pinfunction "1_1") (pintype "passive"))
      (node (ref "U5") (pin "20") (pinfunction "PB2_20") (pintype "bidirectional"))
    )
    (net (code "70") (name "Net-(U5A-PB10)") (class "Default")
      (node (ref "R17") (pin "1") (pinfunction "1_1") (pintype "passive"))
      (node (ref "U5") (pin "21") (pinfunction "PB10_21") (pintype "bidirectional"))
    )
    (net (code "71") (name "Net-(U5A-PB12)") (class "Default")
      (node (ref "U5") (pin "25") (pinfunction "PB12_25") (pintype "bidirectional"))
      (node (ref "U6") (pin "11") (pinfunction "A_11") (pintype "input"))
    )
    (net (code "72") (name "Net-(U5A-PB14)") (class "Default")
      (node (ref "U5") (pin "27") (pinfunction "PB14_27") (pintype "bidirectional"))
      (node (ref "U6") (pin "3") (pinfunction "A_3") (pintype "input"))
    )
    (net (code "73") (name "Net-(U5A-PB15)") (class "Default")
      (node (ref "U5") (pin "28") (pinfunction "PB15_28") (pintype "bidirectional"))
      (node (ref "U6") (pin "9") (pinfunction "A_9") (pintype "input"))
    )
    (net (code "74") (name "Net-(U5A-PD0-OSC_IN)") (class "Default")
      (node (ref "C4") (pin "1") (pinfunction "1_1") (pintype "passive"))
      (node (ref "U5") (pin "5") (pinfunction "PD0-OSC_IN_5") (pintype "bidirectional"))
      (node (ref "ZQ1") (pin "2") (pinfunction "2_2") (pintype "passive"))
    )
    (net (code "75") (name "Net-(U5A-PD1-OSC_OUT)") (class "Default")
      (node (ref "C7") (pin "1") (pinfunction "1_1") (pintype "passive"))
      (node (ref "U5") (pin "6") (pinfunction "PD1-OSC_OUT_6") (pintype "bidirectional"))
      (node (ref "ZQ1") (pin "1") (pinfunction "1_1") (pintype "passive"))
    )
    (net (code "76") (name "Net-(U6A-A)") (class "Default")
      (node (ref "C36") (pin "2") (pinfunction "2_2") (pintype "passive"))
      (node (ref "R30") (pin "1") (pinfunction "1_1") (pintype "passive"))
      (node (ref "R37") (pin "2") (pinfunction "2_2") (pintype "passive"))
      (node (ref "U6") (pin "1") (pinfunction "A_1") (pintype "input"))
    )
    (net (code "77") (name "Net-(U6B-Y)") (class "Default")
      (node (ref "R19") (pin "1") (pinfunction "1_1") (pintype "passive"))
      (node (ref "U6") (pin "4") (pinfunction "Y_4") (pintype "output"))
    )
    (net (code "78") (name "Net-(U6C-A)") (class "Default")
      (node (ref "R34") (pin "2") (pinfunction "2_2") (pintype "passive"))
      (node (ref "R38") (pin "2") (pinfunction "2_2") (pintype "passive"))
      (node (ref "U6") (pin "5") (pinfunction "A_5") (pintype "input"))
    )
    (net (code "79") (name "Net-(U6D-Y)") (class "Default")
      (node (ref "J3") (pin "7") (pinfunction "7_7") (pintype "passive"))
      (node (ref "U6") (pin "8") (pinfunction "Y_8") (pintype "output"))
    )
    (net (code "80") (name "Net-(U6E-Y)") (class "Default")
      (node (ref "R11") (pin "2") (pinfunction "2_2") (pintype "passive"))
      (node (ref "U6") (pin "10") (pinfunction "Y_10") (pintype "output"))
      (node (ref "U6") (pin "13") (pinfunction "A_13") (pintype "input"))
    )
    (net (code "81") (name "Net-(U6F-Y)") (class "Default")
      (node (ref "BU1") (pin "2") (pinfunction "2_2") (pintype "passive"))
      (node (ref "U6") (pin "12") (pinfunction "Y_12") (pintype "output"))
    )
    (net (code "82") (name "Net-(U7A-IN+)") (class "Default")
      (node (ref "C32") (pin "2") (pinfunction "2_2") (pintype "passive"))
      (node (ref "R33") (pin "1") (pinfunction "1_1") (pintype "passive"))
      (node (ref "U7") (pin "3") (pinfunction "IN+_3") (pintype "input"))
    )
    (net (code "83") (name "Net-(U7A-IN-)") (class "Default")
      (node (ref "R23") (pin "1") (pinfunction "1_1") (pintype "passive"))
      (node (ref "R24") (pin "2") (pinfunction "2_2") (pintype "passive"))
      (node (ref "U7") (pin "2") (pinfunction "IN-_2") (pintype "input"))
    )
    (net (code "84") (name "Net-(U7A-OUT)") (class "Default")
      (node (ref "R30") (pin "2") (pinfunction "2_2") (pintype "passive"))
      (node (ref "U7") (pin "1") (pinfunction "OUT_1") (pintype "output"))
    )
    (net (code "85") (name "VDD") (class "Default")
      (node (ref "C23") (pin "1") (pinfunction "1_1") (pintype "passive"))
      (node (ref "C5") (pin "2") (pinfunction "2_2") (pintype "passive"))
      (node (ref "J3") (pin "6") (pinfunction "6_6") (pintype "passive"))
      (node (ref "L1") (pin "1") (pinfunction "1_1") (pintype "passive"))
      (node (ref "Q1") (pin "3") (pinfunction "D_3") (pintype "passive"))
      (node (ref "U6") (pin "14") (pinfunction "VDD_14") (pintype "power_in"))
      (node (ref "U7") (pin "8") (pinfunction "V+_8") (pintype "power_in"))
    )
    (net (code "86") (name "unconnected-(H1-D+-Pad3)") (class "Default")
      (node (ref "H1") (pin "3") (pinfunction "D+_3") (pintype "passive"))
    )
    (net (code "87") (name "unconnected-(H1-D--Pad2)") (class "Default")
      (node (ref "H1") (pin "2") (pinfunction "D-_2") (pintype "passive"))
    )
    (net (code "88") (name "unconnected-(H1-Pad4)") (class "Default")
      (node (ref "H1") (pin "4") (pinfunction "4_4") (pintype "passive"))
    )
    (net (code "89") (name "unconnected-(J4-Pad1)") (class "Default")
      (node (ref "J4") (pin "1") (pinfunction "1_1") (pintype "passive"))
    )
    (net (code "90") (name "unconnected-(J4-Pad2)") (class "Default")
      (node (ref "J4") (pin "2") (pinfunction "2_2") (pintype "passive"))
    )
    (net (code "91") (name "unconnected-(J4-Pad3)") (class "Default")
      (node (ref "J4") (pin "3") (pinfunction "3_3") (pintype "passive"))
    )
    (net (code "92") (name "unconnected-(J4-Pad4)") (class "Default")
      (node (ref "J4") (pin "4") (pinfunction "4_4") (pintype "passive"))
    )
    (net (code "93") (name "unconnected-(J4-Pad5)") (class "Default")
      (node (ref "J4") (pin "5") (pinfunction "5_5") (pintype "passive"))
    )
    (net (code "94") (name "unconnected-(J4-Pad6)") (class "Default")
      (node (ref "J4") (pin "6") (pinfunction "6_6") (pintype "passive"))
    )
    (net (code "95") (name "unconnected-(J4-Pad7)") (class "Default")
      (node (ref "J4") (pin "7") (pinfunction "7_7") (pintype "passive"))
    )
    (net (code "96") (name "unconnected-(J4-Pad8)") (class "Default")
      (node (ref "J4") (pin "8") (pinfunction "8_8") (pintype "passive"))
    )
    (net (code "97") (name "unconnected-(U3-Pad1)") (class "Default")
      (node (ref "U3") (pin "1") (pinfunction "1_1") (pintype "passive"))
    )
    (net (code "98") (name "unconnected-(U3-Pad8)") (class "Default")
      (node (ref "U3") (pin "8") (pinfunction "8_8") (pintype "passive"))
    )
    (net (code "99") (name "unconnected-(U4-Pad4)") (class "Default")
      (node (ref "U4") (pin "4") (pinfunction "4_4") (pintype "passive"))
    )
    (net (code "100") (name "unconnected-(U5A-PA1-Pad11)") (class "Default")
      (node (ref "U5") (pin "11") (pinfunction "PA1_11") (pintype "bidirectional"))
    )
    (net (code "101") (name "unconnected-(U5A-PA3-Pad13)") (class "Default")
      (node (ref "U5") (pin "13") (pinfunction "PA3_13") (pintype "bidirectional"))
    )
    (net (code "102") (name "unconnected-(U5A-PA4-Pad14)") (class "Default")
      (node (ref "U5") (pin "14") (pinfunction "PA4_14") (pintype "bidirectional"))
    )
    (net (code "103") (name "unconnected-(U5A-PA5-Pad15)") (class "Default")
      (node (ref "U5") (pin "15") (pinfunction "PA5_15") (pintype "bidirectional"))
    )
    (net (code "104") (name "unconnected-(U5A-PA6-Pad16)") (class "Default")
      (node (ref "U5") (pin "16") (pinfunction "PA6_16") (pintype "bidirectional"))
    )
    (net (code "105") (name "unconnected-(U5A-PA15-Pad38)") (class "Default")
      (node (ref "U5") (pin "38") (pinfunction "PA15_38") (pintype "bidirectional"))
    )
    (net (code "106") (name "unconnected-(U5A-PB3-Pad39)") (class "Default")
      (node (ref "U5") (pin "39") (pinfunction "PB3_39") (pintype "bidirectional"))
    )
    (net (code "107") (name "unconnected-(U5A-PB4-Pad40)") (class "Default")
      (node (ref "U5") (pin "40") (pinfunction "PB4_40") (pintype "bidirectional"))
    )
    (net (code "108") (name "unconnected-(U5A-PB5-Pad41)") (class "Default")
      (node (ref "U5") (pin "41") (pinfunction "PB5_41") (pintype "bidirectional"))
    )
    (net (code "109") (name "unconnected-(U5A-PB6-Pad42)") (class "Default")
      (node (ref "U5") (pin "42") (pinfunction "PB6_42") (pintype "bidirectional"))
    )
    (net (code "110") (name "unconnected-(U5A-PB7-Pad43)") (class "Default")
      (node (ref "U5") (pin "43") (pinfunction "PB7_43") (pintype "bidirectional"))
    )
    (net (code "111") (name "unconnected-(U5A-PB8-Pad45)") (class "Default")
      (node (ref "U5") (pin "45") (pinfunction "PB8_45") (pintype "bidirectional"))
    )
    (net (code "112") (name "unconnected-(U5A-PB9-Pad46)") (class "Default")
      (node (ref "U5") (pin "46") (pinfunction "PB9_46") (pintype "bidirectional"))
    )
    (net (code "113") (name "unconnected-(U5A-PB11-Pad22)") (class "Default")
      (node (ref "U5") (pin "22") (pinfunction "PB11_22") (pintype "bidirectional"))
    )
    (net (code "114") (name "unconnected-(U5A-PB13-Pad26)") (class "Default")
      (node (ref "U5") (pin "26") (pinfunction "PB13_26") (pintype "bidirectional"))
    )
    (net (code "115") (name "unconnected-(U5A-PC13-TAMPER-RTC-Pad2)") (class "Default")
      (node (ref "U5") (pin "2") (pinfunction "PC13-TAMPER-RTC_2") (pintype "bidirectional"))
    )
    (net (code "116") (name "unconnected-(U5A-PC14-OSC32_IN-Pad3)") (class "Default")
      (node (ref "U5") (pin "3") (pinfunction "PC14-OSC32_IN_3") (pintype "bidirectional"))
    )
    (net (code "117") (name "unconnected-(U5A-PC15-OSC32_OUT-Pad4)") (class "Default")
      (node (ref "U5") (pin "4") (pinfunction "PC15-OSC32_OUT_4") (pintype "bidirectional"))
    )
    (net (code "118") (name "unconnected-(U7B-OUT-Pad7)") (class "Default")
      (node (ref "U7") (pin "7") (pinfunction "OUT_7") (pintype "output"))
    )
  )
)
